# the_staff_2.net
KiCad netlist of a schematic drawn in EAGLE
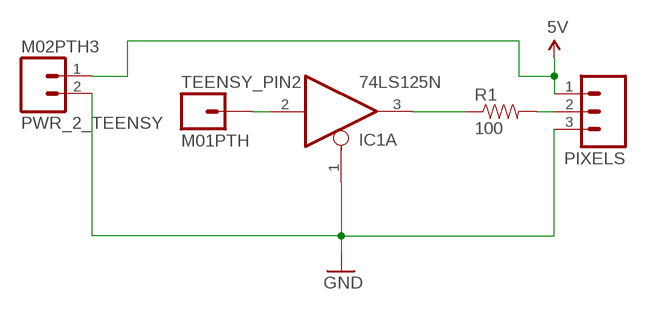
[diagram p0: schematic, sheet 1]

(export (version "E")
  (design (tool "Eeschema 10.0.6"))
  (components
    (comp (ref "IC1")
      (value "74LS125N")
      (footprint "eagle-import:DIL14")
      (libsource (lib "eagle-import") (part "74125NLS"))
    )
    (comp (ref "PIXELS")
      (value "M03LONGPADS")
      (footprint "eagle-import:1X03_LONGPADS")
      (libsource (lib "eagle-import") (part "M03LONGPADS"))
    )
    (comp (ref "PWR_2_TEENSY")
      (value "M02PTH3")
      (footprint "eagle-import:1X02_LONGPADS")
      (libsource (lib "eagle-import") (part "M02PTH3"))
    )
    (comp (ref "R1")
      (value "100")
      (footprint "eagle-import:AXIAL-0.4")
      (libsource (lib "eagle-import") (part "RESISTORPTH-1/4W"))
    )
    (comp (ref "TEENSY_PIN2")
      (value "M01PTH")
      (footprint "eagle-import:1X01")
      (libsource (lib "eagle-import") (part "M01PTH"))
    )
  )
  (nets
    (net (code "1") (name "5V") (class "Default")
      (node (ref "PIXELS") (pin "1") (pinfunction "1_1") (pintype "passive"))
      (node (ref "PWR_2_TEENSY") (pin "1") (pinfunction "1_1") (pintype "passive"))
    )
    (net (code "2") (name "GND") (class "Default")
      (node (ref "IC1") (pin "1") (pinfunction "OE_1") (pintype "input"))
      (node (ref "PIXELS") (pin "3") (pinfunction "3_3") (pintype "passive"))
      (node (ref "PWR_2_TEENSY") (pin "2") (pinfunction "2_2") (pintype "passive"))
    )
    (net (code "3") (name "Net-(IC1A-I)") (class "Default")
      (node (ref "IC1") (pin "2") (pinfunction "I_2") (pintype "input"))
      (node (ref "TEENSY_PIN2") (pin "1") (pinfunction "1_1") (pintype "passive"))
    )
    (net (code "4") (name "Net-(IC1A-O)") (class "Default")
      (node (ref "IC1") (pin "3") (pinfunction "O_3") (pintype "tri_state"))
      (node (ref "R1") (pin "P$1") (pinfunction "1_P$1") (pintype "passive"))
    )
    (net (code "5") (name "Net-(R1-2)") (class "Default")
      (node (ref "PIXELS") (pin "2") (pinfunction "2_2") (pintype "passive"))
      (node (ref "R1") (pin "P$2") (pinfunction "2_P$2") (pintype "passive"))
    )
  )
)
